# Processor.net
KiCad netlist of a schematic drawn in Altium Designer
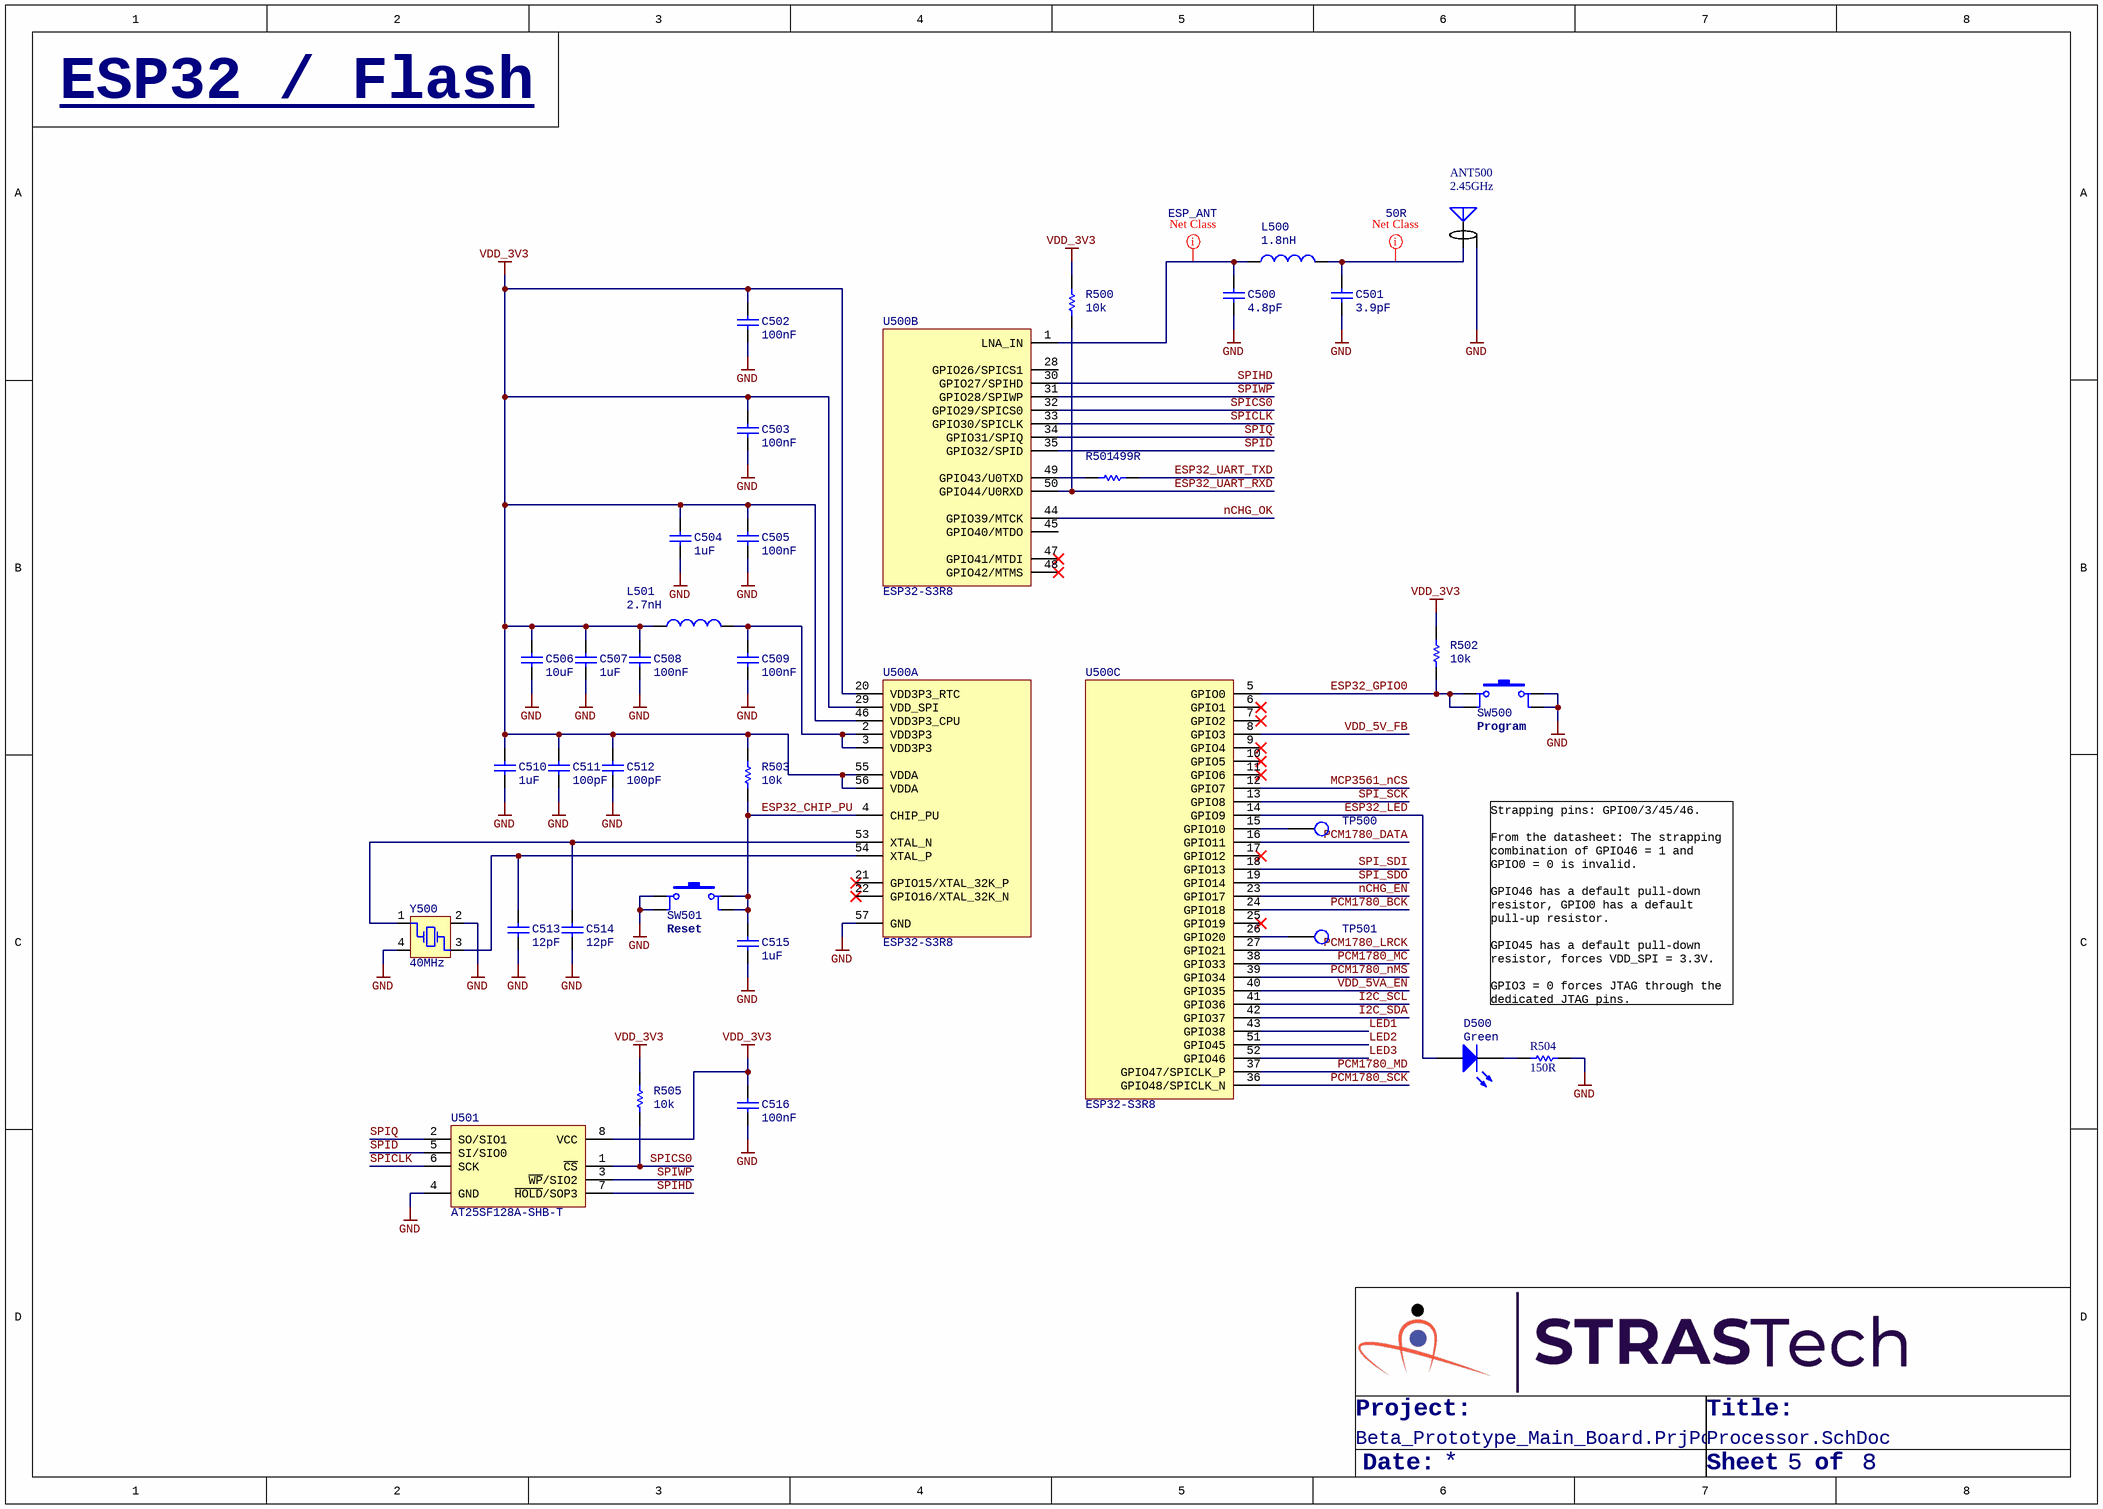
[diagram p0: Processor.SchDoc]

(export (version "E")
  (design (tool "Eeschema 10.0.6"))
  (components
    (comp (ref "ANT500")
      (value "2.45GHz")
      (footprint "ANT,PCB,IFA,2.45GHZ")
      (description "2.4-GHz Inverted F Antenna")
      (fields (field (name "CREATEDBY") "Judd Foster"))
      (libsource (lib "symbols") (part "ANT,2.45GHz,IFA,PCB"))
    )
    (comp (ref "C500")
      (value "4.8pF")
      (footprint "Cap,SMD,0402")
      (description "4.8 pF ±0.25pF 50V Ceramic Capacitor C0G, NP0 0402 (1005 Metric)")
      (fields
        (field (name "VENDOR PART NUMBER") "490-17481-1-ND")
        (field (name "MANUFACTURER") "Murata Electronics")
        (field (name "CREATEDBY") "Judd Foster")
      )
      (libsource (lib "symbols") (part "CAP,Cer,4.8pF,50VDC,C0G/NP0,0402"))
    )
    (comp (ref "C501")
      (value "3.9pF")
      (footprint "Cap,SMD,0402")
      (description "3.9 pF ±0.1pF 50V Ceramic Capacitor C0G, NP0 0402 (1005 Metric)")
      (fields
        (field (name "VENDOR PART NUMBER") "399-CBR04C399B5GACCT-ND")
        (field (name "MANUFACTURER") "KEMET")
        (field (name "CREATEDBY") "Judd Foster")
      )
      (libsource (lib "symbols") (part "CAP,Cer,3.9pF,50VDC,C0G/NP0,0402"))
    )
    (comp (ref "C502")
      (value "100nF")
      (footprint "Cap,SMD,0402")
      (description "0.1µF ±10% 25V Ceramic Capacitor X7R 0402 (1005 Metric)")
      (fields
        (field (name "VENDOR PART NUMBER") "490-14603-1-ND")
        (field (name "MANUFACTURER") "Murata Electronics")
        (field (name "CREATEDBY") "Judd Foster")
      )
      (libsource (lib "symbols") (part "CAP,Cer,100nF,25VDC,X7R,0402"))
    )
    (comp (ref "C503")
      (value "100nF")
      (footprint "Cap,SMD,0402")
      (description "0.1µF ±10% 25V Ceramic Capacitor X7R 0402 (1005 Metric)")
      (fields
        (field (name "VENDOR PART NUMBER") "490-14603-1-ND")
        (field (name "MANUFACTURER") "Murata Electronics")
        (field (name "CREATEDBY") "Judd Foster")
      )
      (libsource (lib "symbols") (part "CAP,Cer,100nF,25VDC,X7R,0402"))
    )
    (comp (ref "C504")
      (value "1uF")
      (footprint "Cap,SMD,0402")
      (description "1 µF ±10% 35V Ceramic Capacitor X5R 0402 (1005 Metric)")
      (fields
        (field (name "VENDOR PART NUMBER") "445-9073-1-ND")
        (field (name "MANUFACTURER") "TDK Corporation")
        (field (name "CREATEDBY") "Judd Foster")
      )
      (libsource (lib "symbols") (part "CAP,Cer,1uF,35VDC,X5R,0402"))
    )
    (comp (ref "C505")
      (value "100nF")
      (footprint "Cap,SMD,0402")
      (description "0.1µF ±10% 25V Ceramic Capacitor X7R 0402 (1005 Metric)")
      (fields
        (field (name "VENDOR PART NUMBER") "490-14603-1-ND")
        (field (name "MANUFACTURER") "Murata Electronics")
        (field (name "CREATEDBY") "Judd Foster")
      )
      (libsource (lib "symbols") (part "CAP,Cer,100nF,25VDC,X7R,0402"))
    )
    (comp (ref "C506")
      (value "10uF")
      (footprint "Cap,SMD,0402")
      (description "10 µF ±20% 10V Ceramic Capacitor X5R 0402 (1005 Metric)")
      (fields
        (field (name "VENDOR PART NUMBER") "1276-1450-1-ND")
        (field (name "MANUFACTURER") "Samsung Electro-Mechanics")
        (field (name "CREATEDBY") "Judd Foster")
      )
      (libsource (lib "symbols") (part "CAP,Cer,10uF,10VDC,X5R,0402"))
    )
    (comp (ref "C507")
      (value "1uF")
      (footprint "Cap,SMD,0402")
      (description "1 µF ±10% 35V Ceramic Capacitor X5R 0402 (1005 Metric)")
      (fields
        (field (name "VENDOR PART NUMBER") "445-9073-1-ND")
        (field (name "MANUFACTURER") "TDK Corporation")
        (field (name "CREATEDBY") "Judd Foster")
      )
      (libsource (lib "symbols") (part "CAP,Cer,1uF,35VDC,X5R,0402"))
    )
    (comp (ref "C508")
      (value "100nF")
      (footprint "Cap,SMD,0402")
      (description "0.1µF ±10% 25V Ceramic Capacitor X7R 0402 (1005 Metric)")
      (fields
        (field (name "VENDOR PART NUMBER") "490-14603-1-ND")
        (field (name "MANUFACTURER") "Murata Electronics")
        (field (name "CREATEDBY") "Judd Foster")
      )
      (libsource (lib "symbols") (part "CAP,Cer,100nF,25VDC,X7R,0402"))
    )
    (comp (ref "C509")
      (value "100nF")
      (footprint "Cap,SMD,0402")
      (description "0.1µF ±10% 25V Ceramic Capacitor X7R 0402 (1005 Metric)")
      (fields
        (field (name "VENDOR PART NUMBER") "490-14603-1-ND")
        (field (name "MANUFACTURER") "Murata Electronics")
        (field (name "CREATEDBY") "Judd Foster")
      )
      (libsource (lib "symbols") (part "CAP,Cer,100nF,25VDC,X7R,0402"))
    )
    (comp (ref "C510")
      (value "1uF")
      (footprint "Cap,SMD,0402")
      (description "1 µF ±10% 35V Ceramic Capacitor X5R 0402 (1005 Metric)")
      (fields
        (field (name "VENDOR PART NUMBER") "445-9073-1-ND")
        (field (name "MANUFACTURER") "TDK Corporation")
        (field (name "CREATEDBY") "Judd Foster")
      )
      (libsource (lib "symbols") (part "CAP,Cer,1uF,35VDC,X5R,0402"))
    )
    (comp (ref "C511")
      (value "100pF")
      (footprint "Cap,SMD,0402")
      (description "100pF ±5% 50V Ceramic Capacitor C0G, NP0 0402 (1005 Metric)")
      (fields
        (field (name "VENDOR PART NUMBER") "490-10669-1-ND")
        (field (name "MANUFACTURER") "Murata Electronics")
        (field (name "CREATEDBY") "Judd Foster")
      )
      (libsource (lib "symbols") (part "CAP,Cer,100pF,50VDC,C0G/NP0,0402"))
    )
    (comp (ref "C512")
      (value "100pF")
      (footprint "Cap,SMD,0402")
      (description "100pF ±5% 50V Ceramic Capacitor C0G, NP0 0402 (1005 Metric)")
      (fields
        (field (name "VENDOR PART NUMBER") "490-10669-1-ND")
        (field (name "MANUFACTURER") "Murata Electronics")
        (field (name "CREATEDBY") "Judd Foster")
      )
      (libsource (lib "symbols") (part "CAP,Cer,100pF,50VDC,C0G/NP0,0402"))
    )
    (comp (ref "C513")
      (value "12pF")
      (footprint "Cap,SMD,0402")
      (description "12pF ±5% 50V Ceramic Capacitor C0G, NP0 0402 (1005 Metric)")
      (fields
        (field (name "VENDOR PART NUMBER") "311-1016-1-ND")
        (field (name "MANUFACTURER") "Yageo")
        (field (name "CREATEDBY") "Judd Foster")
      )
      (libsource (lib "symbols") (part "CAP,Cer,12pF,50VDC,C0G/NP0,0402"))
    )
    (comp (ref "C514")
      (value "12pF")
      (footprint "Cap,SMD,0402")
      (description "12pF ±5% 50V Ceramic Capacitor C0G, NP0 0402 (1005 Metric)")
      (fields
        (field (name "VENDOR PART NUMBER") "311-1016-1-ND")
        (field (name "MANUFACTURER") "Yageo")
        (field (name "CREATEDBY") "Judd Foster")
      )
      (libsource (lib "symbols") (part "CAP,Cer,12pF,50VDC,C0G/NP0,0402"))
    )
    (comp (ref "C515")
      (value "1uF")
      (footprint "Cap,SMD,0402")
      (description "1µF ±20% 6.3V Ceramic Capacitor X5R 0402 (1005 Metric)")
      (fields
        (field (name "VENDOR PART NUMBER") "1276-1235-1-ND")
        (field (name "MANUFACTURER") "Samsung Electro-Mechanics")
        (field (name "CREATEDBY") "Judd Foster")
      )
      (libsource (lib "symbols") (part "CAP,Cer,1uF,6.3VDC,X5R,0402"))
    )
    (comp (ref "C516")
      (value "100nF")
      (footprint "Cap,SMD,0402")
      (description "0.1µF ±10% 25V Ceramic Capacitor X7R 0402 (1005 Metric)")
      (fields
        (field (name "VENDOR PART NUMBER") "490-14603-1-ND")
        (field (name "MANUFACTURER") "Murata Electronics")
        (field (name "CREATEDBY") "Judd Foster")
      )
      (libsource (lib "symbols") (part "CAP,Cer,100nF,25VDC,X7R,0402"))
    )
    (comp (ref "D500")
      (value "Green")
      (footprint "LED,0603")
      (description "Green 530nm LED Indication - Discrete 3V 0603 (1608 Metric)")
      (fields
        (field (name "MANUFACTURER") "Stanley Electric Co")
        (field (name "MANUFACTURER PART NUMBER") "THG1111C-0005-TR")
        (field (name "CREATEDBY") "Judd Foster")
      )
      (libsource (lib "symbols") (part "LED,Green,SMD,0603"))
    )
    (comp (ref "L500")
      (value "1.8nH")
      (footprint "ind,0402")
      (description "1.8 nH Unshielded Multilayer Inductor 900 mA 100mOhm Max 0402 (1005 Metric)")
      (fields
        (field (name "VENDOR PART NUMBER") "490-1076-1-ND")
        (field (name "MANUFACTURER") "Murata Electronics")
        (field (name "CREATEDBY") "Judd Foster")
      )
      (libsource (lib "symbols") (part "IND,1.8nH,900mA,Multilayer,0402"))
    )
    (comp (ref "L501")
      (value "2.7nH")
      (footprint "ind,0402")
      (description "2.7nH Unshielded Multilayer Inductor 800mA 150mOhm Max 0402 (1005 Metric)")
      (fields
        (field (name "VENDOR PART NUMBER") "490-2615-1-ND")
        (field (name "MANUFACTURER") "Murata Electronics")
        (field (name "CREATEDBY") "Judd Foster")
      )
      (libsource (lib "symbols") (part "IND,2.7nH,800mA,Multilayer,0402"))
    )
    (comp (ref "R500")
      (value "10k")
      (footprint "RES,0402")
      (description "10 kOhms ±5% 0.063W, 1/16W Chip Resistor 0402 (1005 Metric) Automotive AEC-Q200 Thick Film")
      (fields
        (field (name "VENDOR PART NUMBER") "RMCF0402JT10K0CT-ND")
        (field (name "MANUFACTURER") "Stackpole Electronics Inc")
        (field (name "CREATEDBY") "Judd Foster")
      )
      (libsource (lib "symbols") (part "RES,10k,5%,0.063W,0402"))
    )
    (comp (ref "R501")
      (value "499R")
      (footprint "RES,0402")
      (description "499 Ohms ±1% 0.063W, 1/16W Chip Resistor 0402 (1005 Metric) Automotive AEC-Q200 Thick Film")
      (fields
        (field (name "MANUFACTURER") "Stackpole Electronics Inc")
        (field (name "MANUFACTURER PART NUMBER") "RMCF0402FT499R")
        (field (name "CREATEDBY") "Judd Foster")
      )
      (libsource (lib "symbols") (part "RES,499R,1%,0.063W,0402"))
    )
    (comp (ref "R502")
      (value "10k")
      (footprint "RES,0402")
      (description "10 kOhms ±5% 0.063W, 1/16W Chip Resistor 0402 (1005 Metric) Automotive AEC-Q200 Thick Film")
      (fields
        (field (name "VENDOR PART NUMBER") "RMCF0402JT10K0CT-ND")
        (field (name "MANUFACTURER") "Stackpole Electronics Inc")
        (field (name "CREATEDBY") "Judd Foster")
      )
      (libsource (lib "symbols") (part "RES,10k,5%,0.063W,0402"))
    )
    (comp (ref "R503")
      (value "10k")
      (footprint "RES,0402")
      (description "10 kOhms ±5% 0.063W, 1/16W Chip Resistor 0402 (1005 Metric) Automotive AEC-Q200 Thick Film")
      (fields
        (field (name "VENDOR PART NUMBER") "RMCF0402JT10K0CT-ND")
        (field (name "MANUFACTURER") "Stackpole Electronics Inc")
        (field (name "CREATEDBY") "Judd Foster")
      )
      (libsource (lib "symbols") (part "RES,10k,5%,0.063W,0402"))
    )
    (comp (ref "R504")
      (value "150R")
      (footprint "RES,0402")
      (fields
        (field (name "MANUFACTURER") "TE Connectivity Passive Product")
        (field (name "MANUFACTURER PART NUMBER") "CRGCQ0402F150R")
        (field (name "VENDOR PART NUMBER") "A129617CT-ND")
        (field (name "CREATEDBY") "Judd Foster")
      )
      (libsource (lib "symbols") (part "RES,150R,1%,0.1W,0402"))
    )
    (comp (ref "R505")
      (value "10k")
      (footprint "RES,0402")
      (description "10 kOhms ±5% 0.063W, 1/16W Chip Resistor 0402 (1005 Metric) Automotive AEC-Q200 Thick Film")
      (fields
        (field (name "VENDOR PART NUMBER") "RMCF0402JT10K0CT-ND")
        (field (name "MANUFACTURER") "Stackpole Electronics Inc")
        (field (name "CREATEDBY") "Judd Foster")
      )
      (libsource (lib "symbols") (part "RES,10k,5%,0.063W,0402"))
    )
    (comp (ref "SW500")
      (value "Switch")
      (footprint "Switch,Tactile,Micro,SPST-NO,SMD")
      (description "Tactile Switch SPST-NO Top Actuated Surface Mount")
      (fields
        (field (name "MANUFACTURER") "C&K")
        (field (name "MANUFACTURER PART NUMBER") "PTS525SM15SMTR2 LFS")
        (field (name "CREATEDBY") "Judd Foster")
      )
      (libsource (lib "symbols") (part "Switch,Tactile,SPST-NO,SMD,H1.5"))
    )
    (comp (ref "SW501")
      (value "Switch")
      (footprint "Switch,Tactile,Micro,SPST-NO,SMD")
      (description "Tactile Switch SPST-NO Top Actuated Surface Mount")
      (fields
        (field (name "MANUFACTURER") "C&K")
        (field (name "MANUFACTURER PART NUMBER") "PTS525SM15SMTR2 LFS")
        (field (name "CREATEDBY") "Judd Foster")
      )
      (libsource (lib "symbols") (part "Switch,Tactile,SPST-NO,SMD,H1.5"))
    )
    (comp (ref "TP500")
      (value "TESTPOINT")
      (footprint "testpoint,smd,round,1mm")
      (description "PCB Testpoint")
      (fields (field (name "CREATEDBY") "Judd Foster"))
      (libsource (lib "symbols") (part "TESTPOINT"))
    )
    (comp (ref "TP501")
      (value "TESTPOINT")
      (footprint "testpoint,smd,round,1mm")
      (description "PCB Testpoint")
      (fields (field (name "CREATEDBY") "Judd Foster"))
      (libsource (lib "symbols") (part "TESTPOINT"))
    )
    (comp (ref "U500")
      (value "ESP32-S3R8")
      (footprint "IC,QFN-56,7X7,P0.4MM")
      (fields
        (field (name "MANUFACTURER") "Espressif Systems")
        (field (name "VENDOR PART NUMBER") "1904-ESP32-S3R8-ND")
        (field (name "CREATEDBY") "Judd Foster")
      )
      (libsource (lib "symbols") (part "ESP32-S3R8"))
    )
    (comp (ref "U501")
      (value "AT25SF128A-SHB-T")
      (footprint "IC,SOIC-8,1.27mm,W5.28")
      (description "FLASH - NOR Memory IC 128Mb (16M x 8) SPI - Quad I/O 133 MHz 8-SOIC")
      (fields
        (field (name "MANUFACTURER") "Adesto Technologies")
        (field (name "VENDOR PART NUMBER") "1265-1348-1-ND")
        (field (name "CREATEDBY") "Judd Foster")
      )
      (libsource (lib "symbols") (part "AT25SF128A-SHB-T"))
    )
    (comp (ref "Y500")
      (value "40MHz")
      (footprint "XTAL,SMD,4 Pin,2x2.5mm")
      (description "40 MHz ±7ppm Crystal 12pF 25 Ohms 4-SMD, No Lead")
      (fields
        (field (name "MANUFACTURER") "Hosonic Electronic Co., Ltd")
        (field (name "MANUFACTURER PART NUMBER") "E2SB40E000104E")
        (field (name "CREATEDBY") "Judd Foster")
      )
      (libsource (lib "symbols") (part "XTAL,40MHz,12pF,SMD"))
    )
  )
  (nets
    (net (code "1") (name "/ESP32_CHIP_PU") (class "Default")
      (node (ref "C515") (pin "2") (pinfunction "2_2") (pintype "passive"))
      (node (ref "R503") (pin "2") (pinfunction "2_2") (pintype "passive"))
      (node (ref "SW501") (pin "3") (pinfunction "3_3") (pintype "passive"))
      (node (ref "SW501") (pin "4") (pinfunction "4_4") (pintype "passive"))
      (node (ref "U500") (pin "4") (pinfunction "CHIP_PU_4") (pintype "passive"))
    )
    (net (code "2") (name "/ESP32_GPIO0") (class "Default")
      (node (ref "R502") (pin "2") (pinfunction "2_2") (pintype "passive"))
      (node (ref "SW500") (pin "1") (pinfunction "1_1") (pintype "passive"))
      (node (ref "SW500") (pin "2") (pinfunction "2_2") (pintype "passive"))
      (node (ref "U500") (pin "5") (pinfunction "GPIO0_5") (pintype "passive"))
    )
    (net (code "3") (name "/ESP32_LED") (class "Default")
      (node (ref "D500") (pin "1") (pinfunction "A_1") (pintype "passive"))
      (node (ref "U500") (pin "14") (pinfunction "GPIO9_14") (pintype "passive"))
    )
    (net (code "4") (name "/ESP32_UART_RXD") (class "Default")
      (node (ref "R500") (pin "1") (pinfunction "1_1") (pintype "passive"))
      (node (ref "U500") (pin "50") (pinfunction "GPIO44/U0RXD_50") (pintype "passive"))
    )
    (net (code "5") (name "/ESP32_UART_TXD") (class "Default")
      (node (ref "R501") (pin "2") (pinfunction "2_2") (pintype "passive"))
    )
    (net (code "6") (name "/I2C_SCL") (class "Default")
      (node (ref "U500") (pin "41") (pinfunction "GPIO36_41") (pintype "passive"))
    )
    (net (code "7") (name "/I2C_SDA") (class "Default")
      (node (ref "U500") (pin "42") (pinfunction "GPIO37_42") (pintype "passive"))
    )
    (net (code "8") (name "/LED1") (class "Default")
      (node (ref "U500") (pin "43") (pinfunction "GPIO38_43") (pintype "passive"))
    )
    (net (code "9") (name "/LED2") (class "Default")
      (node (ref "U500") (pin "51") (pinfunction "GPIO45_51") (pintype "passive"))
    )
    (net (code "10") (name "/LED3") (class "Default")
      (node (ref "U500") (pin "52") (pinfunction "GPIO46_52") (pintype "passive"))
    )
    (net (code "11") (name "/MCP3561_nCS") (class "Default")
      (node (ref "U500") (pin "12") (pinfunction "GPIO7_12") (pintype "passive"))
    )
    (net (code "12") (name "/PCM1780_BCK") (class "Default")
      (node (ref "U500") (pin "24") (pinfunction "GPIO18_24") (pintype "passive"))
    )
    (net (code "13") (name "/PCM1780_DATA") (class "Default")
      (node (ref "U500") (pin "16") (pinfunction "GPIO11_16") (pintype "passive"))
    )
    (net (code "14") (name "/PCM1780_LRCK") (class "Default")
      (node (ref "U500") (pin "27") (pinfunction "GPIO21_27") (pintype "passive"))
    )
    (net (code "15") (name "/PCM1780_MC") (class "Default")
      (node (ref "U500") (pin "38") (pinfunction "GPIO33_38") (pintype "passive"))
    )
    (net (code "16") (name "/PCM1780_MD") (class "Default")
      (node (ref "U500") (pin "37") (pinfunction "GPIO47/SPICLK_P_37") (pintype "passive"))
    )
    (net (code "17") (name "/PCM1780_SCK") (class "Default")
      (node (ref "U500") (pin "36") (pinfunction "GPIO48/SPICLK_N_36") (pintype "passive"))
    )
    (net (code "18") (name "/PCM1780_nMS") (class "Default")
      (node (ref "U500") (pin "39") (pinfunction "GPIO34_39") (pintype "passive"))
    )
    (net (code "19") (name "/SPICLK") (class "Default")
      (node (ref "U500") (pin "33") (pinfunction "GPIO30/SPICLK_33") (pintype "passive"))
      (node (ref "U501") (pin "6") (pinfunction "SCK_6") (pintype "passive"))
    )
    (net (code "20") (name "/SPICS0") (class "Default")
      (node (ref "R505") (pin "1") (pinfunction "1_1") (pintype "passive"))
      (node (ref "U500") (pin "32") (pinfunction "GPIO29/SPICS0_32") (pintype "passive"))
      (node (ref "U501") (pin "1") (pinfunction "~{CS}_1") (pintype "passive"))
    )
    (net (code "21") (name "/SPID") (class "Default")
      (node (ref "U500") (pin "35") (pinfunction "GPIO32/SPID_35") (pintype "passive"))
      (node (ref "U501") (pin "5") (pinfunction "SI/SIO0_5") (pintype "passive"))
    )
    (net (code "22") (name "/SPIHD") (class "Default")
      (node (ref "U500") (pin "30") (pinfunction "GPIO27/SPIHD_30") (pintype "passive"))
      (node (ref "U501") (pin "7") (pinfunction "~{HOLD}/SOP3_7") (pintype "passive"))
    )
    (net (code "23") (name "/SPIQ") (class "Default")
      (node (ref "U500") (pin "34") (pinfunction "GPIO31/SPIQ_34") (pintype "passive"))
      (node (ref "U501") (pin "2") (pinfunction "SO/SIO1_2") (pintype "passive"))
    )
    (net (code "24") (name "/SPIWP") (class "Default")
      (node (ref "U500") (pin "31") (pinfunction "GPIO28/SPIWP_31") (pintype "passive"))
      (node (ref "U501") (pin "3") (pinfunction "~{WP}/SIO2_3") (pintype "passive"))
    )
    (net (code "25") (name "/SPI_SCK") (class "Default")
      (node (ref "U500") (pin "13") (pinfunction "GPIO8_13") (pintype "passive"))
    )
    (net (code "26") (name "/SPI_SDI") (class "Default")
      (node (ref "U500") (pin "18") (pinfunction "GPIO13_18") (pintype "passive"))
    )
    (net (code "27") (name "/SPI_SDO") (class "Default")
      (node (ref "U500") (pin "19") (pinfunction "GPIO14_19") (pintype "passive"))
    )
    (net (code "28") (name "/VDD_5VA_EN") (class "Default")
      (node (ref "U500") (pin "40") (pinfunction "GPIO35_40") (pintype "passive"))
    )
    (net (code "29") (name "/VDD_5V_FB") (class "Default")
      (node (ref "U500") (pin "8") (pinfunction "GPIO3_8") (pintype "passive"))
    )
    (net (code "30") (name "/nCHG_EN") (class "Default")
      (node (ref "U500") (pin "23") (pinfunction "GPIO17_23") (pintype "passive"))
    )
    (net (code "31") (name "/nCHG_OK") (class "Default")
      (node (ref "U500") (pin "44") (pinfunction "GPIO39/MTCK_44") (pintype "passive"))
    )
    (net (code "32") (name "GND") (class "Default")
      (node (ref "ANT500") (pin "2") (pinfunction "2_2") (pintype "passive"))
      (node (ref "C500") (pin "1") (pinfunction "1_1") (pintype "passive"))
      (node (ref "C501") (pin "1") (pinfunction "1_1") (pintype "passive"))
      (node (ref "C502") (pin "1") (pinfunction "1_1") (pintype "passive"))
      (node (ref "C503") (pin "1") (pinfunction "1_1") (pintype "passive"))
      (node (ref "C504") (pin "1") (pinfunction "1_1") (pintype "passive"))
      (node (ref "C505") (pin "1") (pinfunction "1_1") (pintype "passive"))
      (node (ref "C506") (pin "1") (pinfunction "1_1") (pintype "passive"))
      (node (ref "C507") (pin "1") (pinfunction "1_1") (pintype "passive"))
      (node (ref "C508") (pin "1") (pinfunction "1_1") (pintype "passive"))
      (node (ref "C509") (pin "1") (pinfunction "1_1") (pintype "passive"))
      (node (ref "C510") (pin "1") (pinfunction "1_1") (pintype "passive"))
      (node (ref "C511") (pin "1") (pinfunction "1_1") (pintype "passive"))
      (node (ref "C512") (pin "1") (pinfunction "1_1") (pintype "passive"))
      (node (ref "C513") (pin "2") (pinfunction "2_2") (pintype "passive"))
      (node (ref "C514") (pin "2") (pinfunction "2_2") (pintype "passive"))
      (node (ref "C515") (pin "1") (pinfunction "1_1") (pintype "passive"))
      (node (ref "C516") (pin "1") (pinfunction "1_1") (pintype "passive"))
      (node (ref "R504") (pin "2") (pinfunction "2_2") (pintype "passive"))
      (node (ref "SW500") (pin "3") (pinfunction "3_3") (pintype "passive"))
      (node (ref "SW500") (pin "4") (pinfunction "4_4") (pintype "passive"))
      (node (ref "SW501") (pin "1") (pinfunction "1_1") (pintype "passive"))
      (node (ref "SW501") (pin "2") (pinfunction "2_2") (pintype "passive"))
      (node (ref "U500") (pin "57") (pinfunction "GND_57") (pintype "passive"))
      (node (ref "U501") (pin "4") (pinfunction "GND_4") (pintype "passive"))
      (node (ref "Y500") (pin "2") (pinfunction "GND_2") (pintype "passive"))
      (node (ref "Y500") (pin "4") (pinfunction "GND_4") (pintype "passive"))
    )
    (net (code "33") (name "Net-(ANT500-Pad1)") (class "Default")
      (node (ref "ANT500") (pin "1") (pinfunction "1_1") (pintype "passive"))
      (node (ref "C501") (pin "2") (pinfunction "2_2") (pintype "passive"))
      (node (ref "L500") (pin "2") (pinfunction "2_2") (pintype "passive"))
    )
    (net (code "34") (name "Net-(C509-Pad2)") (class "Default")
      (node (ref "C509") (pin "2") (pinfunction "2_2") (pintype "passive"))
      (node (ref "L501") (pin "2") (pinfunction "2_2") (pintype "passive"))
      (node (ref "U500") (pin "2") (pinfunction "VDD3P3_2") (pintype "passive"))
      (node (ref "U500") (pin "3") (pinfunction "VDD3P3_3") (pintype "passive"))
    )
    (net (code "35") (name "Net-(D500-K)") (class "Default")
      (node (ref "D500") (pin "2") (pinfunction "K_2") (pintype "passive"))
      (node (ref "R504") (pin "1") (pinfunction "1_1") (pintype "passive"))
    )
    (net (code "36") (name "Net-(TP500-TP)") (class "Default")
      (node (ref "TP500") (pin "1") (pinfunction "TP_1") (pintype "passive"))
      (node (ref "U500") (pin "15") (pinfunction "GPIO10_15") (pintype "passive"))
    )
    (net (code "37") (name "Net-(TP501-TP)") (class "Default")
      (node (ref "TP501") (pin "1") (pinfunction "TP_1") (pintype "passive"))
      (node (ref "U500") (pin "26") (pinfunction "GPIO20_26") (pintype "passive"))
    )
    (net (code "38") (name "Net-(U500A-XTAL_N)") (class "Default")
      (node (ref "C514") (pin "1") (pinfunction "1_1") (pintype "passive"))
      (node (ref "U500") (pin "53") (pinfunction "XTAL_N_53") (pintype "passive"))
      (node (ref "Y500") (pin "1") (pinfunction "OSC1_1") (pintype "passive"))
    )
    (net (code "39") (name "Net-(U500A-XTAL_P)") (class "Default")
      (node (ref "C513") (pin "1") (pinfunction "1_1") (pintype "passive"))
      (node (ref "U500") (pin "54") (pinfunction "XTAL_P_54") (pintype "passive"))
      (node (ref "Y500") (pin "3") (pinfunction "OSC2_3") (pintype "passive"))
    )
    (net (code "40") (name "Net-(U500B-GPIO43{slash}U0TXD)") (class "Default")
      (node (ref "R501") (pin "1") (pinfunction "1_1") (pintype "passive"))
      (node (ref "U500") (pin "49") (pinfunction "GPIO43/U0TXD_49") (pintype "passive"))
    )
    (net (code "41") (name "Net-(U500B-LNA_IN)") (class "Default")
      (node (ref "C500") (pin "2") (pinfunction "2_2") (pintype "passive"))
      (node (ref "L500") (pin "1") (pinfunction "1_1") (pintype "passive"))
      (node (ref "U500") (pin "1") (pinfunction "LNA_IN_1") (pintype "passive"))
    )
    (net (code "42") (name "VDD_3V3") (class "Default")
      (node (ref "C502") (pin "2") (pinfunction "2_2") (pintype "passive"))
      (node (ref "C503") (pin "2") (pinfunction "2_2") (pintype "passive"))
      (node (ref "C504") (pin "2") (pinfunction "2_2") (pintype "passive"))
      (node (ref "C505") (pin "2") (pinfunction "2_2") (pintype "passive"))
      (node (ref "C506") (pin "2") (pinfunction "2_2") (pintype "passive"))
      (node (ref "C507") (pin "2") (pinfunction "2_2") (pintype "passive"))
      (node (ref "C508") (pin "2") (pinfunction "2_2") (pintype "passive"))
      (node (ref "C510") (pin "2") (pinfunction "2_2") (pintype "passive"))
      (node (ref "C511") (pin "2") (pinfunction "2_2") (pintype "passive"))
      (node (ref "C512") (pin "2") (pinfunction "2_2") (pintype "passive"))
      (node (ref "C516") (pin "2") (pinfunction "2_2") (pintype "passive"))
      (node (ref "L501") (pin "1") (pinfunction "1_1") (pintype "passive"))
      (node (ref "R500") (pin "2") (pinfunction "2_2") (pintype "passive"))
      (node (ref "R502") (pin "1") (pinfunction "1_1") (pintype "passive"))
      (node (ref "R503") (pin "1") (pinfunction "1_1") (pintype "passive"))
      (node (ref "R505") (pin "2") (pinfunction "2_2") (pintype "passive"))
      (node (ref "U500") (pin "20") (pinfunction "VDD3P3_RTC_20") (pintype "passive"))
      (node (ref "U500") (pin "29") (pinfunction "VDD_SPI_29") (pintype "passive"))
      (node (ref "U500") (pin "46") (pinfunction "VDD3P3_CPU_46") (pintype "passive"))
      (node (ref "U500") (pin "55") (pinfunction "VDDA_55") (pintype "passive"))
      (node (ref "U500") (pin "56") (pinfunction "VDDA_56") (pintype "passive"))
      (node (ref "U501") (pin "8") (pinfunction "VCC_8") (pintype "passive"))
    )
    (net (code "43") (name "unconnected-(U500A-GPIO15{slash}XTAL_32K_P-Pad21)") (class "Default")
      (node (ref "U500") (pin "21") (pinfunction "GPIO15/XTAL_32K_P_21") (pintype "passive+no_connect"))
    )
    (net (code "44") (name "unconnected-(U500A-GPIO16{slash}XTAL_32K_N-Pad22)") (class "Default")
      (node (ref "U500") (pin "22") (pinfunction "GPIO16/XTAL_32K_N_22") (pintype "passive+no_connect"))
    )
    (net (code "45") (name "unconnected-(U500B-GPIO26{slash}SPICS1-Pad28)") (class "Default")
      (node (ref "U500") (pin "28") (pinfunction "GPIO26/SPICS1_28") (pintype "passive"))
    )
    (net (code "46") (name "unconnected-(U500B-GPIO40{slash}MTDO-Pad45)") (class "Default")
      (node (ref "U500") (pin "45") (pinfunction "GPIO40/MTDO_45") (pintype "passive"))
    )
    (net (code "47") (name "unconnected-(U500B-GPIO41{slash}MTDI-Pad47)") (class "Default")
      (node (ref "U500") (pin "47") (pinfunction "GPIO41/MTDI_47") (pintype "passive+no_connect"))
    )
    (net (code "48") (name "unconnected-(U500B-GPIO42{slash}MTMS-Pad48)") (class "Default")
      (node (ref "U500") (pin "48") (pinfunction "GPIO42/MTMS_48") (pintype "passive+no_connect"))
    )
    (net (code "49") (name "unconnected-(U500C-GPIO1-Pad6)") (class "Default")
      (node (ref "U500") (pin "6") (pinfunction "GPIO1_6") (pintype "passive+no_connect"))
    )
    (net (code "50") (name "unconnected-(U500C-GPIO2-Pad7)") (class "Default")
      (node (ref "U500") (pin "7") (pinfunction "GPIO2_7") (pintype "passive+no_connect"))
    )
    (net (code "51") (name "unconnected-(U500C-GPIO4-Pad9)") (class "Default")
      (node (ref "U500") (pin "9") (pinfunction "GPIO4_9") (pintype "passive+no_connect"))
    )
    (net (code "52") (name "unconnected-(U500C-GPIO5-Pad10)") (class "Default")
      (node (ref "U500") (pin "10") (pinfunction "GPIO5_10") (pintype "passive+no_connect"))
    )
    (net (code "53") (name "unconnected-(U500C-GPIO6-Pad11)") (class "Default")
      (node (ref "U500") (pin "11") (pinfunction "GPIO6_11") (pintype "passive+no_connect"))
    )
    (net (code "54") (name "unconnected-(U500C-GPIO12-Pad17)") (class "Default")
      (node (ref "U500") (pin "17") (pinfunction "GPIO12_17") (pintype "passive+no_connect"))
    )
    (net (code "55") (name "unconnected-(U500C-GPIO19-Pad25)") (class "Default")
      (node (ref "U500") (pin "25") (pinfunction "GPIO19_25") (pintype "passive+no_connect"))
    )
  )
)
